# APM9328_CONNECTORR.net
KiCad netlist of a schematic drawn in Altium Designer
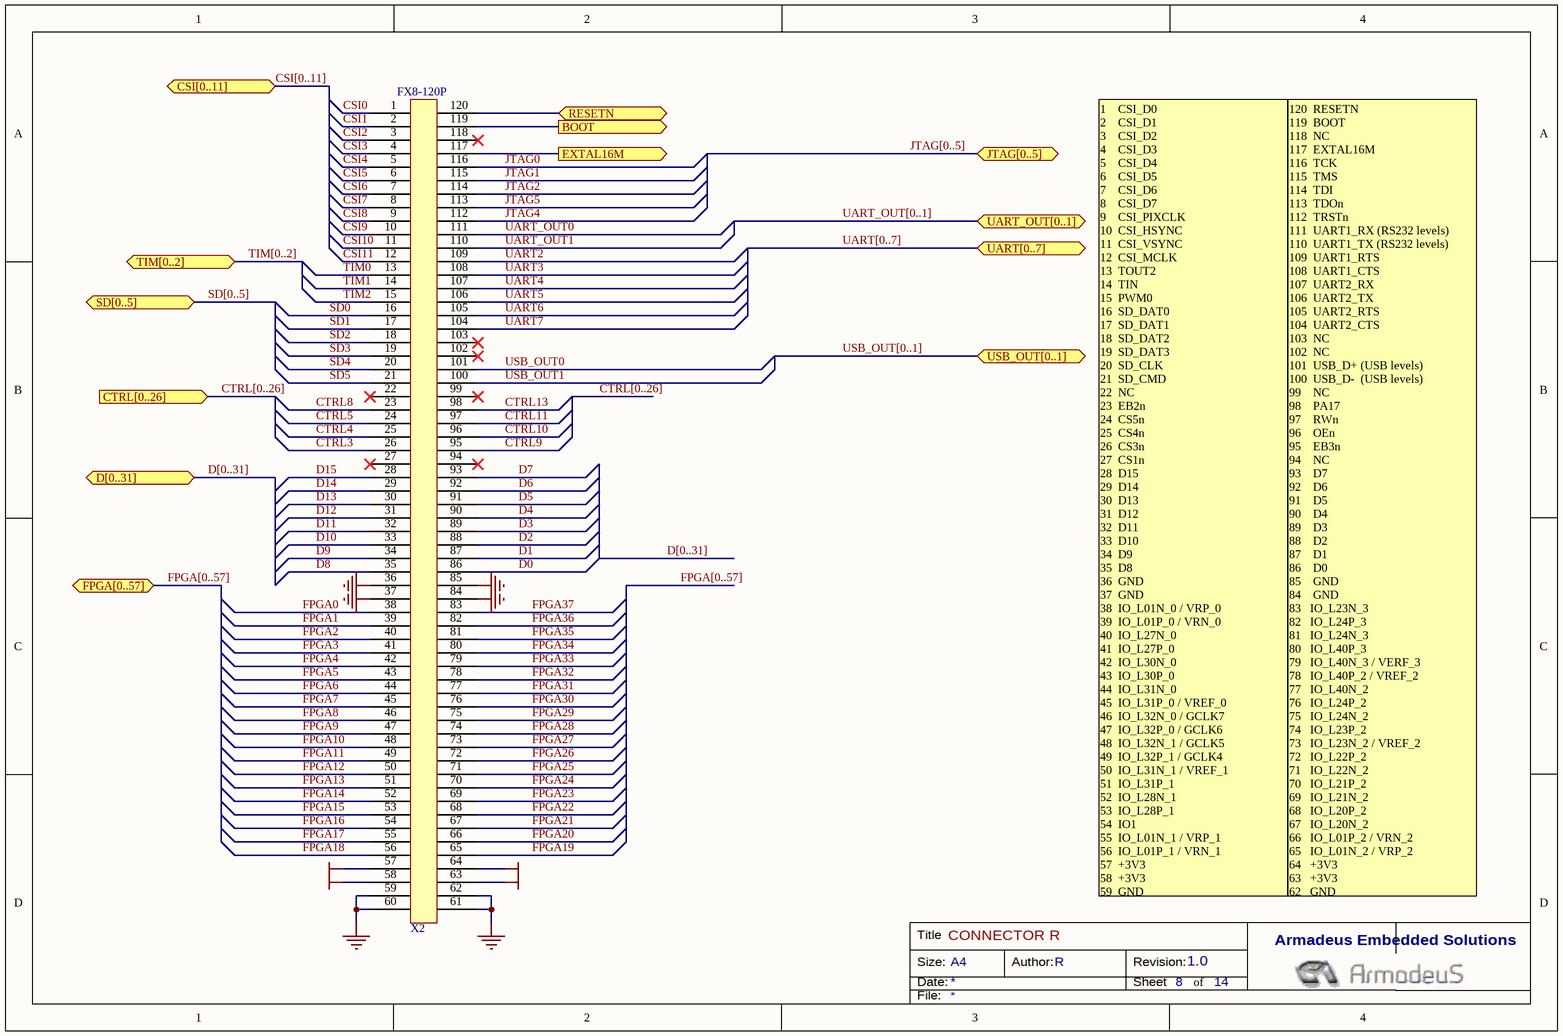
[diagram p0: APM9328_CONNECTORR.SchDoc]

(export (version "E")
  (design (tool "Eeschema 10.0.6"))
  (components
    (comp (ref "X2")
      (value "FX8-120P")
      (footprint "FX8-120P")
      (description "Fine Pitch Connector")
      (fields (field (name "MANUFACTURER") "Hirose") (field (name "PART NUMBER") "FX8-120P-SV"))
      (libsource (lib "*") (part "FX8-120P"))
    )
  )
  (nets
    (net (code "59") (name "+3V3") (class "Default")
      (node (ref "X2") (pin "57") (pintype "passive"))
      (node (ref "X2") (pin "58") (pintype "passive"))
      (node (ref "X2") (pin "63") (pintype "passive"))
      (node (ref "X2") (pin "64") (pintype "passive"))
    )
    (net (code "60") (name "/BOOT") (class "Default") (node (ref "X2") (pin "119") (pintype "passive")))
    (net (code "61") (name "/CSI0") (class "Default") (node (ref "X2") (pin "1") (pintype "passive")))
    (net (code "62") (name "/CSI1") (class "Default") (node (ref "X2") (pin "2") (pintype "passive")))
    (net (code "63") (name "/CSI2") (class "Default") (node (ref "X2") (pin "3") (pintype "passive")))
    (net (code "64") (name "/CSI3") (class "Default") (node (ref "X2") (pin "4") (pintype "passive")))
    (net (code "65") (name "/CSI4") (class "Default") (node (ref "X2") (pin "5") (pintype "passive")))
    (net (code "66") (name "/CSI5") (class "Default") (node (ref "X2") (pin "6") (pintype "passive")))
    (net (code "67") (name "/CSI6") (class "Default") (node (ref "X2") (pin "7") (pintype "passive")))
    (net (code "68") (name "/CSI7") (class "Default") (node (ref "X2") (pin "8") (pintype "passive")))
    (net (code "69") (name "/CSI8") (class "Default") (node (ref "X2") (pin "9") (pintype "passive")))
    (net (code "70") (name "/CSI9") (class "Default") (node (ref "X2") (pin "10") (pintype "passive")))
    (net (code "71") (name "/CSI10") (class "Default") (node (ref "X2") (pin "11") (pintype "passive")))
    (net (code "72") (name "/CSI11") (class "Default") (node (ref "X2") (pin "12") (pintype "passive")))
    (net (code "74") (name "/CTRL3") (class "Default") (node (ref "X2") (pin "26") (pintype "passive")))
    (net (code "75") (name "/CTRL4") (class "Default") (node (ref "X2") (pin "25") (pintype "passive")))
    (net (code "76") (name "/CTRL5") (class "Default") (node (ref "X2") (pin "24") (pintype "passive")))
    (net (code "77") (name "/CTRL8") (class "Default") (node (ref "X2") (pin "23") (pintype "passive")))
    (net (code "78") (name "/CTRL9") (class "Default") (node (ref "X2") (pin "95") (pintype "passive")))
    (net (code "79") (name "/CTRL10") (class "Default") (node (ref "X2") (pin "96") (pintype "passive")))
    (net (code "80") (name "/CTRL11") (class "Default") (node (ref "X2") (pin "97") (pintype "passive")))
    (net (code "81") (name "/CTRL13") (class "Default") (node (ref "X2") (pin "98") (pintype "passive")))
    (net (code "83") (name "/D0") (class "Default") (node (ref "X2") (pin "86") (pintype "passive")))
    (net (code "84") (name "/D1") (class "Default") (node (ref "X2") (pin "87") (pintype "passive")))
    (net (code "85") (name "/D2") (class "Default") (node (ref "X2") (pin "88") (pintype "passive")))
    (net (code "86") (name "/D3") (class "Default") (node (ref "X2") (pin "89") (pintype "passive")))
    (net (code "87") (name "/D4") (class "Default") (node (ref "X2") (pin "90") (pintype "passive")))
    (net (code "88") (name "/D5") (class "Default") (node (ref "X2") (pin "91") (pintype "passive")))
    (net (code "89") (name "/D6") (class "Default") (node (ref "X2") (pin "92") (pintype "passive")))
    (net (code "90") (name "/D7") (class "Default") (node (ref "X2") (pin "93") (pintype "passive")))
    (net (code "91") (name "/D8") (class "Default") (node (ref "X2") (pin "35") (pintype "passive")))
    (net (code "92") (name "/D9") (class "Default") (node (ref "X2") (pin "34") (pintype "passive")))
    (net (code "93") (name "/D10") (class "Default") (node (ref "X2") (pin "33") (pintype "passive")))
    (net (code "94") (name "/D11") (class "Default") (node (ref "X2") (pin "32") (pintype "passive")))
    (net (code "95") (name "/D12") (class "Default") (node (ref "X2") (pin "31") (pintype "passive")))
    (net (code "96") (name "/D13") (class "Default") (node (ref "X2") (pin "30") (pintype "passive")))
    (net (code "97") (name "/D14") (class "Default") (node (ref "X2") (pin "29") (pintype "passive")))
    (net (code "98") (name "/D15") (class "Default") (node (ref "X2") (pin "28") (pintype "passive")))
    (net (code "100") (name "/EXTAL16M") (class "Default") (node (ref "X2") (pin "117") (pintype "passive")))
    (net (code "101") (name "/FPGA0") (class "Default") (node (ref "X2") (pin "38") (pintype "passive")))
    (net (code "102") (name "/FPGA1") (class "Default") (node (ref "X2") (pin "39") (pintype "passive")))
    (net (code "103") (name "/FPGA2") (class "Default") (node (ref "X2") (pin "40") (pintype "passive")))
    (net (code "104") (name "/FPGA3") (class "Default") (node (ref "X2") (pin "41") (pintype "passive")))
    (net (code "105") (name "/FPGA4") (class "Default") (node (ref "X2") (pin "42") (pintype "passive")))
    (net (code "106") (name "/FPGA5") (class "Default") (node (ref "X2") (pin "43") (pintype "passive")))
    (net (code "107") (name "/FPGA6") (class "Default") (node (ref "X2") (pin "44") (pintype "passive")))
    (net (code "108") (name "/FPGA7") (class "Default") (node (ref "X2") (pin "45") (pintype "passive")))
    (net (code "109") (name "/FPGA8") (class "Default") (node (ref "X2") (pin "46") (pintype "passive")))
    (net (code "110") (name "/FPGA9") (class "Default") (node (ref "X2") (pin "47") (pintype "passive")))
    (net (code "111") (name "/FPGA10") (class "Default") (node (ref "X2") (pin "48") (pintype "passive")))
    (net (code "112") (name "/FPGA11") (class "Default") (node (ref "X2") (pin "49") (pintype "passive")))
    (net (code "113") (name "/FPGA12") (class "Default") (node (ref "X2") (pin "50") (pintype "passive")))
    (net (code "114") (name "/FPGA13") (class "Default") (node (ref "X2") (pin "51") (pintype "passive")))
    (net (code "115") (name "/FPGA14") (class "Default") (node (ref "X2") (pin "52") (pintype "passive")))
    (net (code "116") (name "/FPGA15") (class "Default") (node (ref "X2") (pin "53") (pintype "passive")))
    (net (code "117") (name "/FPGA16") (class "Default") (node (ref "X2") (pin "54") (pintype "passive")))
    (net (code "118") (name "/FPGA17") (class "Default") (node (ref "X2") (pin "55") (pintype "passive")))
    (net (code "119") (name "/FPGA18") (class "Default") (node (ref "X2") (pin "56") (pintype "passive")))
    (net (code "120") (name "/FPGA19") (class "Default") (node (ref "X2") (pin "65") (pintype "passive")))
    (net (code "121") (name "/FPGA20") (class "Default") (node (ref "X2") (pin "66") (pintype "passive")))
    (net (code "122") (name "/FPGA21") (class "Default") (node (ref "X2") (pin "67") (pintype "passive")))
    (net (code "123") (name "/FPGA22") (class "Default") (node (ref "X2") (pin "68") (pintype "passive")))
    (net (code "124") (name "/FPGA23") (class "Default") (node (ref "X2") (pin "69") (pintype "passive")))
    (net (code "125") (name "/FPGA24") (class "Default") (node (ref "X2") (pin "70") (pintype "passive")))
    (net (code "126") (name "/FPGA25") (class "Default") (node (ref "X2") (pin "71") (pintype "passive")))
    (net (code "127") (name "/FPGA26") (class "Default") (node (ref "X2") (pin "72") (pintype "passive")))
    (net (code "128") (name "/FPGA27") (class "Default") (node (ref "X2") (pin "73") (pintype "passive")))
    (net (code "129") (name "/FPGA28") (class "Default") (node (ref "X2") (pin "74") (pintype "passive")))
    (net (code "130") (name "/FPGA29") (class "Default") (node (ref "X2") (pin "75") (pintype "passive")))
    (net (code "131") (name "/FPGA30") (class "Default") (node (ref "X2") (pin "76") (pintype "passive")))
    (net (code "132") (name "/FPGA31") (class "Default") (node (ref "X2") (pin "77") (pintype "passive")))
    (net (code "133") (name "/FPGA32") (class "Default") (node (ref "X2") (pin "78") (pintype "passive")))
    (net (code "134") (name "/FPGA33") (class "Default") (node (ref "X2") (pin "79") (pintype "passive")))
    (net (code "135") (name "/FPGA34") (class "Default") (node (ref "X2") (pin "80") (pintype "passive")))
    (net (code "136") (name "/FPGA35") (class "Default") (node (ref "X2") (pin "81") (pintype "passive")))
    (net (code "137") (name "/FPGA36") (class "Default") (node (ref "X2") (pin "82") (pintype "passive")))
    (net (code "138") (name "/FPGA37") (class "Default") (node (ref "X2") (pin "83") (pintype "passive")))
    (net (code "140") (name "/JTAG0") (class "Default") (node (ref "X2") (pin "116") (pintype "passive")))
    (net (code "141") (name "/JTAG1") (class "Default") (node (ref "X2") (pin "115") (pintype "passive")))
    (net (code "142") (name "/JTAG2") (class "Default") (node (ref "X2") (pin "114") (pintype "passive")))
    (net (code "143") (name "/JTAG4") (class "Default") (node (ref "X2") (pin "112") (pintype "passive")))
    (net (code "144") (name "/JTAG5") (class "Default") (node (ref "X2") (pin "113") (pintype "passive")))
    (net (code "146") (name "/RESETN") (class "Default") (node (ref "X2") (pin "120") (pintype "passive")))
    (net (code "147") (name "/SD0") (class "Default") (node (ref "X2") (pin "16") (pintype "passive")))
    (net (code "148") (name "/SD1") (class "Default") (node (ref "X2") (pin "17") (pintype "passive")))
    (net (code "149") (name "/SD2") (class "Default") (node (ref "X2") (pin "18") (pintype "passive")))
    (net (code "150") (name "/SD3") (class "Default") (node (ref "X2") (pin "19") (pintype "passive")))
    (net (code "151") (name "/SD4") (class "Default") (node (ref "X2") (pin "20") (pintype "passive")))
    (net (code "152") (name "/SD5") (class "Default") (node (ref "X2") (pin "21") (pintype "passive")))
    (net (code "154") (name "/TIM0") (class "Default") (node (ref "X2") (pin "13") (pintype "passive")))
    (net (code "155") (name "/TIM1") (class "Default") (node (ref "X2") (pin "14") (pintype "passive")))
    (net (code "156") (name "/TIM2") (class "Default") (node (ref "X2") (pin "15") (pintype "passive")))
    (net (code "158") (name "/UART2") (class "Default") (node (ref "X2") (pin "109") (pintype "passive")))
    (net (code "159") (name "/UART3") (class "Default") (node (ref "X2") (pin "108") (pintype "passive")))
    (net (code "160") (name "/UART4") (class "Default") (node (ref "X2") (pin "107") (pintype "passive")))
    (net (code "161") (name "/UART5") (class "Default") (node (ref "X2") (pin "106") (pintype "passive")))
    (net (code "162") (name "/UART6") (class "Default") (node (ref "X2") (pin "105") (pintype "passive")))
    (net (code "163") (name "/UART7") (class "Default") (node (ref "X2") (pin "104") (pintype "passive")))
    (net (code "165") (name "/UART_OUT0") (class "Default") (node (ref "X2") (pin "111") (pintype "passive")))
    (net (code "166") (name "/UART_OUT1") (class "Default") (node (ref "X2") (pin "110") (pintype "passive")))
    (net (code "168") (name "/USB_OUT0") (class "Default") (node (ref "X2") (pin "101") (pintype "passive")))
    (net (code "169") (name "/USB_OUT1") (class "Default") (node (ref "X2") (pin "100") (pintype "passive")))
    (net (code "171") (name "GND") (class "Default")
      (node (ref "X2") (pin "36") (pintype "passive"))
      (node (ref "X2") (pin "37") (pintype "passive"))
      (node (ref "X2") (pin "59") (pintype "passive"))
      (node (ref "X2") (pin "60") (pintype "passive"))
      (node (ref "X2") (pin "61") (pintype "passive"))
      (node (ref "X2") (pin "62") (pintype "passive"))
      (node (ref "X2") (pin "84") (pintype "passive"))
      (node (ref "X2") (pin "85") (pintype "passive"))
    )
    (net (code "172") (name "unconnected-(X2-Pad22)") (class "Default")
      (node (ref "X2") (pin "22") (pintype "passive+no_connect"))
    )
    (net (code "173") (name "unconnected-(X2-Pad27)") (class "Default")
      (node (ref "X2") (pin "27") (pintype "passive+no_connect"))
    )
    (net (code "174") (name "unconnected-(X2-Pad94)") (class "Default")
      (node (ref "X2") (pin "94") (pintype "passive+no_connect"))
    )
    (net (code "175") (name "unconnected-(X2-Pad99)") (class "Default")
      (node (ref "X2") (pin "99") (pintype "passive+no_connect"))
    )
    (net (code "176") (name "unconnected-(X2-Pad102)") (class "Default")
      (node (ref "X2") (pin "102") (pintype "passive+no_connect"))
    )
    (net (code "177") (name "unconnected-(X2-Pad103)") (class "Default")
      (node (ref "X2") (pin "103") (pintype "passive+no_connect"))
    )
    (net (code "178") (name "unconnected-(X2-Pad118)") (class "Default")
      (node (ref "X2") (pin "118") (pintype "passive+no_connect"))
    )
  )
)
